# 05_eMMC.net
KiCad netlist of a schematic drawn in Altium Designer
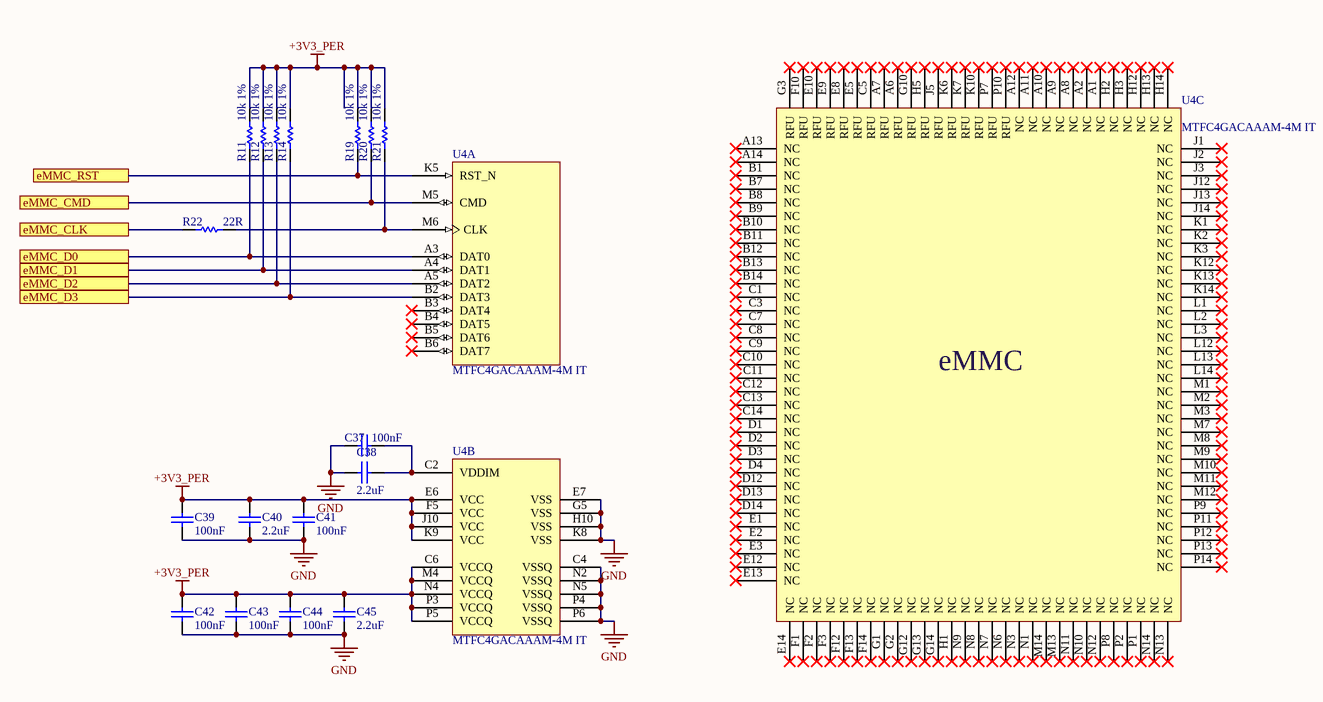
[diagram p0: 05. eMMC.SchDoc]

(export (version "E")
  (design (tool "Eeschema 10.0.6"))
  (components
    (comp (ref "C37")
      (value "100nF")
      (footprint "CAPC1005X60X30LL05T10")
      (description "Chip Capacitor, 0.1 uF, +/- 10%, 16 V, -55 to 125 degC, 0402 (1005 Metric), RoHS, Tape and Reel")
      (fields (field (name "VOLTAGE") "16V") (field (name "TOLERANCE") "10%"))
      (libsource (lib "AM3358_DEV_BOARD") (part "CAP-NP-2"))
    )
    (comp (ref "C38")
      (value "2.2uF")
      (footprint "CAPC1608X90X35ML10T15")
      (description "CAP 2.2uF 10V ±10% 0603 (1608 Metric) Thickness 0.6mm SMD")
      (fields (field (name "MANUFACTURER") "Murata") (field (name "PART NUMBER") "GRM188R71A225KE15D"))
      (libsource (lib "Altium Content Vault") (part "CAP"))
    )
    (comp (ref "C39")
      (value "100nF")
      (footprint "CAPC1005X60X30LL05T10")
      (description "Chip Capacitor, 0.1 uF, +/- 10%, 16 V, -55 to 125 degC, 0402 (1005 Metric), RoHS, Tape and Reel")
      (fields (field (name "VOLTAGE") "16V") (field (name "TOLERANCE") "10%"))
      (libsource (lib "AM3358_DEV_BOARD") (part "CAP-NP-2"))
    )
    (comp (ref "C40")
      (value "2.2uF")
      (footprint "CAPC1005X60X30LL05T10")
      (description "CAP 2.2uF 10V ±10% 0603 (1608 Metric) Thickness 0.6mm SMD")
      (fields (field (name "MANUFACTURER") "Murata") (field (name "PART NUMBER") "GRM188R71A225KE15D"))
      (libsource (lib "AM3358_DEV_BOARD") (part "CAP"))
    )
    (comp (ref "C41")
      (value "100nF")
      (footprint "CAPC1005X60X30LL05T10")
      (description "Chip Capacitor, 0.1 uF, +/- 10%, 16 V, -55 to 125 degC, 0402 (1005 Metric), RoHS, Tape and Reel")
      (fields (field (name "VOLTAGE") "16V") (field (name "TOLERANCE") "10%"))
      (libsource (lib "AM3358_DEV_BOARD") (part "CAP-NP-2"))
    )
    (comp (ref "C42")
      (value "100nF")
      (footprint "CAPC1005X60X30LL05T10")
      (description "Chip Capacitor, 0.1 uF, +/- 10%, 16 V, -55 to 125 degC, 0402 (1005 Metric), RoHS, Tape and Reel")
      (fields (field (name "VOLTAGE") "16V") (field (name "TOLERANCE") "10%"))
      (libsource (lib "AM3358_DEV_BOARD") (part "CAP-NP-2"))
    )
    (comp (ref "C43")
      (value "100nF")
      (footprint "CAPC1005X60X30LL05T10")
      (description "Chip Capacitor, 0.1 uF, +/- 10%, 16 V, -55 to 125 degC, 0402 (1005 Metric), RoHS, Tape and Reel")
      (fields (field (name "VOLTAGE") "16V") (field (name "TOLERANCE") "10%"))
      (libsource (lib "AM3358_DEV_BOARD") (part "CAP-NP-2"))
    )
    (comp (ref "C44")
      (value "100nF")
      (footprint "CAPC1005X60X30LL05T10")
      (description "Chip Capacitor, 0.1 uF, +/- 10%, 16 V, -55 to 125 degC, 0402 (1005 Metric), RoHS, Tape and Reel")
      (fields (field (name "VOLTAGE") "16V") (field (name "TOLERANCE") "10%"))
      (libsource (lib "AM3358_DEV_BOARD") (part "CAP-NP-2"))
    )
    (comp (ref "C45")
      (value "2.2uF")
      (footprint "CAPC1608X90X35ML10T15")
      (description "CAP 2.2uF 10V ±10% 0603 (1608 Metric) Thickness 0.6mm SMD")
      (fields (field (name "MANUFACTURER") "Murata") (field (name "PART NUMBER") "GRM188R71A225KE15D"))
      (libsource (lib "Altium Content Vault") (part "CAP"))
    )
    (comp (ref "R11")
      (value "10k 1%")
      (footprint "RESC1005X40X25LL05T05")
      (description "10k 0.063W 1% 0402 (1005 Metric)  SMD")
      (fields (field (name "MANUFACTURER") "Vishay Dale") (field (name "PART NUMBER") "CRCW040210K0FKED"))
      (libsource (lib "AM3358_DEV_BOARD") (part "RES"))
    )
    (comp (ref "R12")
      (value "10k 1%")
      (footprint "RESC1005X40X25LL05T05")
      (description "10k 0.063W 1% 0402 (1005 Metric)  SMD")
      (fields (field (name "MANUFACTURER") "Vishay Dale") (field (name "PART NUMBER") "CRCW040210K0FKED"))
      (libsource (lib "AM3358_DEV_BOARD") (part "RES"))
    )
    (comp (ref "R13")
      (value "10k 1%")
      (footprint "RESC1005X40X25LL05T05")
      (description "10k 0.063W 1% 0402 (1005 Metric)  SMD")
      (fields (field (name "MANUFACTURER") "Vishay Dale") (field (name "PART NUMBER") "CRCW040210K0FKED"))
      (libsource (lib "AM3358_DEV_BOARD") (part "RES"))
    )
    (comp (ref "R14")
      (value "10k 1%")
      (footprint "RESC1005X40X25LL05T05")
      (description "10k 0.063W 1% 0402 (1005 Metric)  SMD")
      (fields (field (name "MANUFACTURER") "Vishay Dale") (field (name "PART NUMBER") "CRCW040210K0FKED"))
      (libsource (lib "AM3358_DEV_BOARD") (part "RES"))
    )
    (comp (ref "R19")
      (value "10k 1%")
      (footprint "RESC1005X40X25LL05T05")
      (description "10k 0.063W 1% 0402 (1005 Metric)  SMD")
      (fields (field (name "MANUFACTURER") "Vishay Dale") (field (name "PART NUMBER") "CRCW040210K0FKED"))
      (libsource (lib "AM3358_DEV_BOARD") (part "RES"))
    )
    (comp (ref "R20")
      (value "10k 1%")
      (footprint "RESC1005X40X25LL05T05")
      (description "10k 0.063W 1% 0402 (1005 Metric)  SMD")
      (fields (field (name "MANUFACTURER") "Vishay Dale") (field (name "PART NUMBER") "CRCW040210K0FKED"))
      (libsource (lib "AM3358_DEV_BOARD") (part "RES"))
    )
    (comp (ref "R21")
      (value "10k 1%")
      (footprint "RESC1005X40X25LL05T05")
      (description "10k 0.063W 1% 0402 (1005 Metric)  SMD")
      (fields (field (name "MANUFACTURER") "Vishay Dale") (field (name "PART NUMBER") "CRCW040210K0FKED"))
      (libsource (lib "AM3358_DEV_BOARD") (part "RES"))
    )
    (comp (ref "R22")
      (value "22R")
      (footprint "RESC1005X40X25LL05T05")
      (description "Chip Resistor, 22 Ohm, +/- 1%, 0.1 W, -55 to 155 degC, 0402 (1005 Metric), RoHS, Tape and Reel")
      (fields (field (name "PARTNUMBER") "ERJ-2RKF22R0X") (field (name "TOLERANCE") "1%"))
      (libsource (lib "AM3358_DEV_BOARD") (part "RES-2"))
    )
    (comp (ref "U4")
      (value "MTFC4GACAAAM-4M IT")
      (footprint "VFBGA-153")
      (description "e·MMC Memory, 4 Gb, 2.7 to 3.6 V, -40 to 85 degC, 153-Ball VFBGA, RoHS")
      (fields (field (name "MANUFACTURER") "Micron"))
      (libsource (lib "AM3358_DEV_BOARD") (part "CMP-2000-05234-1"))
    )
  )
  (nets
    (net (code "1") (name "+3V3_PER") (class "Default")
      (node (ref "C39") (pin "2") (pinfunction "2_2") (pintype "passive"))
      (node (ref "C40") (pin "2") (pinfunction "2_2") (pintype "passive"))
      (node (ref "C41") (pin "2") (pinfunction "2_2") (pintype "passive"))
      (node (ref "C42") (pin "2") (pinfunction "2_2") (pintype "passive"))
      (node (ref "C43") (pin "2") (pinfunction "2_2") (pintype "passive"))
      (node (ref "C44") (pin "2") (pinfunction "2_2") (pintype "passive"))
      (node (ref "C45") (pin "2") (pinfunction "2_2") (pintype "passive"))
      (node (ref "R11") (pin "2") (pinfunction "2_2") (pintype "passive"))
      (node (ref "R12") (pin "2") (pinfunction "2_2") (pintype "passive"))
      (node (ref "R13") (pin "2") (pinfunction "2_2") (pintype "passive"))
      (node (ref "R14") (pin "2") (pinfunction "2_2") (pintype "passive"))
      (node (ref "R19") (pin "2") (pinfunction "2_2") (pintype "passive"))
      (node (ref "R20") (pin "2") (pinfunction "2_2") (pintype "passive"))
      (node (ref "R21") (pin "2") (pinfunction "2_2") (pintype "passive"))
      (node (ref "U4") (pin "C6") (pinfunction "VCCQ_C6") (pintype "power_in"))
      (node (ref "U4") (pin "E6") (pinfunction "VCC_E6") (pintype "power_in"))
      (node (ref "U4") (pin "F5") (pinfunction "VCC_F5") (pintype "power_in"))
      (node (ref "U4") (pin "J10") (pinfunction "VCC_J10") (pintype "power_in"))
      (node (ref "U4") (pin "K9") (pinfunction "VCC_K9") (pintype "power_in"))
      (node (ref "U4") (pin "M4") (pinfunction "VCCQ_M4") (pintype "power_in"))
      (node (ref "U4") (pin "N4") (pinfunction "VCCQ_N4") (pintype "power_in"))
      (node (ref "U4") (pin "P3") (pinfunction "VCCQ_P3") (pintype "power_in"))
      (node (ref "U4") (pin "P5") (pinfunction "VCCQ_P5") (pintype "power_in"))
    )
    (net (code "2") (name "/eMMC_CLK") (class "Default")
      (node (ref "R22") (pin "1") (pinfunction "1_1") (pintype "passive"))
    )
    (net (code "3") (name "/eMMC_CMD") (class "Default")
      (node (ref "R20") (pin "1") (pinfunction "1_1") (pintype "passive"))
      (node (ref "U4") (pin "M5") (pinfunction "CMD_M5") (pintype "bidirectional"))
    )
    (net (code "4") (name "/eMMC_D0") (class "Default")
      (node (ref "R11") (pin "1") (pinfunction "1_1") (pintype "passive"))
      (node (ref "U4") (pin "A3") (pinfunction "DAT0_A3") (pintype "bidirectional"))
    )
    (net (code "5") (name "/eMMC_D1") (class "Default")
      (node (ref "R12") (pin "1") (pinfunction "1_1") (pintype "passive"))
      (node (ref "U4") (pin "A4") (pinfunction "DAT1_A4") (pintype "bidirectional"))
    )
    (net (code "6") (name "/eMMC_D2") (class "Default")
      (node (ref "R13") (pin "1") (pinfunction "1_1") (pintype "passive"))
      (node (ref "U4") (pin "A5") (pinfunction "DAT2_A5") (pintype "bidirectional"))
    )
    (net (code "7") (name "/eMMC_D3") (class "Default")
      (node (ref "R14") (pin "1") (pinfunction "1_1") (pintype "passive"))
      (node (ref "U4") (pin "B2") (pinfunction "DAT3_B2") (pintype "bidirectional"))
    )
    (net (code "8") (name "/eMMC_RST") (class "Default")
      (node (ref "R19") (pin "1") (pinfunction "1_1") (pintype "passive"))
      (node (ref "U4") (pin "K5") (pinfunction "RST_N_K5") (pintype "input"))
    )
    (net (code "9") (name "GND") (class "Default")
      (node (ref "C37") (pin "2") (pinfunction "2_2") (pintype "passive"))
      (node (ref "C38") (pin "2") (pinfunction "2_2") (pintype "passive"))
      (node (ref "C39") (pin "1") (pinfunction "1_1") (pintype "passive"))
      (node (ref "C40") (pin "1") (pinfunction "1_1") (pintype "passive"))
      (node (ref "C41") (pin "1") (pinfunction "1_1") (pintype "passive"))
      (node (ref "C42") (pin "1") (pinfunction "1_1") (pintype "passive"))
      (node (ref "C43") (pin "1") (pinfunction "1_1") (pintype "passive"))
      (node (ref "C44") (pin "1") (pinfunction "1_1") (pintype "passive"))
      (node (ref "C45") (pin "1") (pinfunction "1_1") (pintype "passive"))
      (node (ref "U4") (pin "C4") (pinfunction "VSSQ_C4") (pintype "power_in"))
      (node (ref "U4") (pin "E7") (pinfunction "VSS_E7") (pintype "power_in"))
      (node (ref "U4") (pin "G5") (pinfunction "VSS_G5") (pintype "power_in"))
      (node (ref "U4") (pin "H10") (pinfunction "VSS_H10") (pintype "power_in"))
      (node (ref "U4") (pin "K8") (pinfunction "VSS_K8") (pintype "power_in"))
      (node (ref "U4") (pin "N2") (pinfunction "VSSQ_N2") (pintype "power_in"))
      (node (ref "U4") (pin "N5") (pinfunction "VSSQ_N5") (pintype "power_in"))
      (node (ref "U4") (pin "P4") (pinfunction "VSSQ_P4") (pintype "power_in"))
      (node (ref "U4") (pin "P6") (pinfunction "VSSQ_P6") (pintype "power_in"))
    )
    (net (code "10") (name "Net-(U4A-CLK)") (class "Default")
      (node (ref "R21") (pin "1") (pinfunction "1_1") (pintype "passive"))
      (node (ref "R22") (pin "2") (pinfunction "2_2") (pintype "passive"))
      (node (ref "U4") (pin "M6") (pinfunction "CLK_M6") (pintype "input"))
    )
    (net (code "11") (name "Net-(U4B-VDDIM)") (class "Default")
      (node (ref "C37") (pin "1") (pinfunction "1_1") (pintype "passive"))
      (node (ref "C38") (pin "1") (pinfunction "1_1") (pintype "passive"))
      (node (ref "U4") (pin "C2") (pinfunction "VDDIM_C2") (pintype "power_in"))
    )
    (net (code "12") (name "unconnected-(U4A-DAT4-PadB3)") (class "Default")
      (node (ref "U4") (pin "B3") (pinfunction "DAT4_B3") (pintype "bidirectional+no_connect"))
    )
    (net (code "13") (name "unconnected-(U4A-DAT5-PadB4)") (class "Default")
      (node (ref "U4") (pin "B4") (pinfunction "DAT5_B4") (pintype "bidirectional+no_connect"))
    )
    (net (code "14") (name "unconnected-(U4A-DAT6-PadB5)") (class "Default")
      (node (ref "U4") (pin "B5") (pinfunction "DAT6_B5") (pintype "bidirectional+no_connect"))
    )
    (net (code "15") (name "unconnected-(U4A-DAT7-PadB6)") (class "Default")
      (node (ref "U4") (pin "B6") (pinfunction "DAT7_B6") (pintype "bidirectional+no_connect"))
    )
    (net (code "16") (name "unconnected-(U4C-NC-PadA1)") (class "Default")
      (node (ref "U4") (pin "A1") (pinfunction "NC_A1") (pintype "passive+no_connect"))
    )
    (net (code "17") (name "unconnected-(U4C-NC-PadA2)") (class "Default")
      (node (ref "U4") (pin "A2") (pinfunction "NC_A2") (pintype "passive+no_connect"))
    )
    (net (code "18") (name "unconnected-(U4C-NC-PadA8)") (class "Default")
      (node (ref "U4") (pin "A8") (pinfunction "NC_A8") (pintype "passive+no_connect"))
    )
    (net (code "19") (name "unconnected-(U4C-NC-PadA9)") (class "Default")
      (node (ref "U4") (pin "A9") (pinfunction "NC_A9") (pintype "passive+no_connect"))
    )
    (net (code "20") (name "unconnected-(U4C-NC-PadA10)") (class "Default")
      (node (ref "U4") (pin "A10") (pinfunction "NC_A10") (pintype "passive+no_connect"))
    )
    (net (code "21") (name "unconnected-(U4C-NC-PadA11)") (class "Default")
      (node (ref "U4") (pin "A11") (pinfunction "NC_A11") (pintype "passive+no_connect"))
    )
    (net (code "22") (name "unconnected-(U4C-NC-PadA12)") (class "Default")
      (node (ref "U4") (pin "A12") (pinfunction "NC_A12") (pintype "passive+no_connect"))
    )
    (net (code "23") (name "unconnected-(U4C-NC-PadA13)") (class "Default")
      (node (ref "U4") (pin "A13") (pinfunction "NC_A13") (pintype "passive+no_connect"))
    )
    (net (code "24") (name "unconnected-(U4C-NC-PadA14)") (class "Default")
      (node (ref "U4") (pin "A14") (pinfunction "NC_A14") (pintype "passive+no_connect"))
    )
    (net (code "25") (name "unconnected-(U4C-NC-PadB1)") (class "Default")
      (node (ref "U4") (pin "B1") (pinfunction "NC_B1") (pintype "passive+no_connect"))
    )
    (net (code "26") (name "unconnected-(U4C-NC-PadB7)") (class "Default")
      (node (ref "U4") (pin "B7") (pinfunction "NC_B7") (pintype "passive+no_connect"))
    )
    (net (code "27") (name "unconnected-(U4C-NC-PadB8)") (class "Default")
      (node (ref "U4") (pin "B8") (pinfunction "NC_B8") (pintype "passive+no_connect"))
    )
    (net (code "28") (name "unconnected-(U4C-NC-PadB9)") (class "Default")
      (node (ref "U4") (pin "B9") (pinfunction "NC_B9") (pintype "passive+no_connect"))
    )
    (net (code "29") (name "unconnected-(U4C-NC-PadB10)") (class "Default")
      (node (ref "U4") (pin "B10") (pinfunction "NC_B10") (pintype "passive+no_connect"))
    )
    (net (code "30") (name "unconnected-(U4C-NC-PadB11)") (class "Default")
      (node (ref "U4") (pin "B11") (pinfunction "NC_B11") (pintype "passive+no_connect"))
    )
    (net (code "31") (name "unconnected-(U4C-NC-PadB12)") (class "Default")
      (node (ref "U4") (pin "B12") (pinfunction "NC_B12") (pintype "passive+no_connect"))
    )
    (net (code "32") (name "unconnected-(U4C-NC-PadB13)") (class "Default")
      (node (ref "U4") (pin "B13") (pinfunction "NC_B13") (pintype "passive+no_connect"))
    )
    (net (code "33") (name "unconnected-(U4C-NC-PadB14)") (class "Default")
      (node (ref "U4") (pin "B14") (pinfunction "NC_B14") (pintype "passive+no_connect"))
    )
    (net (code "34") (name "unconnected-(U4C-NC-PadC1)") (class "Default")
      (node (ref "U4") (pin "C1") (pinfunction "NC_C1") (pintype "passive+no_connect"))
    )
    (net (code "35") (name "unconnected-(U4C-NC-PadC3)") (class "Default")
      (node (ref "U4") (pin "C3") (pinfunction "NC_C3") (pintype "passive+no_connect"))
    )
    (net (code "36") (name "unconnected-(U4C-NC-PadC7)") (class "Default")
      (node (ref "U4") (pin "C7") (pinfunction "NC_C7") (pintype "passive+no_connect"))
    )
    (net (code "37") (name "unconnected-(U4C-NC-PadC8)") (class "Default")
      (node (ref "U4") (pin "C8") (pinfunction "NC_C8") (pintype "passive+no_connect"))
    )
    (net (code "38") (name "unconnected-(U4C-NC-PadC9)") (class "Default")
      (node (ref "U4") (pin "C9") (pinfunction "NC_C9") (pintype "passive+no_connect"))
    )
    (net (code "39") (name "unconnected-(U4C-NC-PadC10)") (class "Default")
      (node (ref "U4") (pin "C10") (pinfunction "NC_C10") (pintype "passive+no_connect"))
    )
    (net (code "40") (name "unconnected-(U4C-NC-PadC11)") (class "Default")
      (node (ref "U4") (pin "C11") (pinfunction "NC_C11") (pintype "passive+no_connect"))
    )
    (net (code "41") (name "unconnected-(U4C-NC-PadC12)") (class "Default")
      (node (ref "U4") (pin "C12") (pinfunction "NC_C12") (pintype "passive+no_connect"))
    )
    (net (code "42") (name "unconnected-(U4C-NC-PadC13)") (class "Default")
      (node (ref "U4") (pin "C13") (pinfunction "NC_C13") (pintype "passive+no_connect"))
    )
    (net (code "43") (name "unconnected-(U4C-NC-PadC14)") (class "Default")
      (node (ref "U4") (pin "C14") (pinfunction "NC_C14") (pintype "passive+no_connect"))
    )
    (net (code "44") (name "unconnected-(U4C-NC-PadD1)") (class "Default")
      (node (ref "U4") (pin "D1") (pinfunction "NC_D1") (pintype "passive+no_connect"))
    )
    (net (code "45") (name "unconnected-(U4C-NC-PadD2)") (class "Default")
      (node (ref "U4") (pin "D2") (pinfunction "NC_D2") (pintype "passive+no_connect"))
    )
    (net (code "46") (name "unconnected-(U4C-NC-PadD3)") (class "Default")
      (node (ref "U4") (pin "D3") (pinfunction "NC_D3") (pintype "passive+no_connect"))
    )
    (net (code "47") (name "unconnected-(U4C-NC-PadD4)") (class "Default")
      (node (ref "U4") (pin "D4") (pinfunction "NC_D4") (pintype "passive+no_connect"))
    )
    (net (code "48") (name "unconnected-(U4C-NC-PadD12)") (class "Default")
      (node (ref "U4") (pin "D12") (pinfunction "NC_D12") (pintype "passive+no_connect"))
    )
    (net (code "49") (name "unconnected-(U4C-NC-PadD13)") (class "Default")
      (node (ref "U4") (pin "D13") (pinfunction "NC_D13") (pintype "passive+no_connect"))
    )
    (net (code "50") (name "unconnected-(U4C-NC-PadD14)") (class "Default")
      (node (ref "U4") (pin "D14") (pinfunction "NC_D14") (pintype "passive+no_connect"))
    )
    (net (code "51") (name "unconnected-(U4C-NC-PadE1)") (class "Default")
      (node (ref "U4") (pin "E1") (pinfunction "NC_E1") (pintype "passive+no_connect"))
    )
    (net (code "52") (name "unconnected-(U4C-NC-PadE2)") (class "Default")
      (node (ref "U4") (pin "E2") (pinfunction "NC_E2") (pintype "passive+no_connect"))
    )
    (net (code "53") (name "unconnected-(U4C-NC-PadE3)") (class "Default")
      (node (ref "U4") (pin "E3") (pinfunction "NC_E3") (pintype "passive+no_connect"))
    )
    (net (code "54") (name "unconnected-(U4C-NC-PadE12)") (class "Default")
      (node (ref "U4") (pin "E12") (pinfunction "NC_E12") (pintype "passive+no_connect"))
    )
    (net (code "55") (name "unconnected-(U4C-NC-PadE13)") (class "Default")
      (node (ref "U4") (pin "E13") (pinfunction "NC_E13") (pintype "passive+no_connect"))
    )
    (net (code "56") (name "unconnected-(U4C-NC-PadE14)") (class "Default")
      (node (ref "U4") (pin "E14") (pinfunction "NC_E14") (pintype "passive+no_connect"))
    )
    (net (code "57") (name "unconnected-(U4C-NC-PadF1)") (class "Default")
      (node (ref "U4") (pin "F1") (pinfunction "NC_F1") (pintype "passive+no_connect"))
    )
    (net (code "58") (name "unconnected-(U4C-NC-PadF2)") (class "Default")
      (node (ref "U4") (pin "F2") (pinfunction "NC_F2") (pintype "passive+no_connect"))
    )
    (net (code "59") (name "unconnected-(U4C-NC-PadF3)") (class "Default")
      (node (ref "U4") (pin "F3") (pinfunction "NC_F3") (pintype "passive+no_connect"))
    )
    (net (code "60") (name "unconnected-(U4C-NC-PadF12)") (class "Default")
      (node (ref "U4") (pin "F12") (pinfunction "NC_F12") (pintype "passive+no_connect"))
    )
    (net (code "61") (name "unconnected-(U4C-NC-PadF13)") (class "Default")
      (node (ref "U4") (pin "F13") (pinfunction "NC_F13") (pintype "passive+no_connect"))
    )
    (net (code "62") (name "unconnected-(U4C-NC-PadF14)") (class "Default")
      (node (ref "U4") (pin "F14") (pinfunction "NC_F14") (pintype "passive+no_connect"))
    )
    (net (code "63") (name "unconnected-(U4C-NC-PadG1)") (class "Default")
      (node (ref "U4") (pin "G1") (pinfunction "NC_G1") (pintype "passive+no_connect"))
    )
    (net (code "64") (name "unconnected-(U4C-NC-PadG2)") (class "Default")
      (node (ref "U4") (pin "G2") (pinfunction "NC_G2") (pintype "passive+no_connect"))
    )
    (net (code "65") (name "unconnected-(U4C-NC-PadG12)") (class "Default")
      (node (ref "U4") (pin "G12") (pinfunction "NC_G12") (pintype "passive+no_connect"))
    )
    (net (code "66") (name "unconnected-(U4C-NC-PadG13)") (class "Default")
      (node (ref "U4") (pin "G13") (pinfunction "NC_G13") (pintype "passive+no_connect"))
    )
    (net (code "67") (name "unconnected-(U4C-NC-PadG14)") (class "Default")
      (node (ref "U4") (pin "G14") (pinfunction "NC_G14") (pintype "passive+no_connect"))
    )
    (net (code "68") (name "unconnected-(U4C-NC-PadH1)") (class "Default")
      (node (ref "U4") (pin "H1") (pinfunction "NC_H1") (pintype "passive+no_connect"))
    )
    (net (code "69") (name "unconnected-(U4C-NC-PadH2)") (class "Default")
      (node (ref "U4") (pin "H2") (pinfunction "NC_H2") (pintype "passive+no_connect"))
    )
    (net (code "70") (name "unconnected-(U4C-NC-PadH3)") (class "Default")
      (node (ref "U4") (pin "H3") (pinfunction "NC_H3") (pintype "passive+no_connect"))
    )
    (net (code "71") (name "unconnected-(U4C-NC-PadH12)") (class "Default")
      (node (ref "U4") (pin "H12") (pinfunction "NC_H12") (pintype "passive+no_connect"))
    )
    (net (code "72") (name "unconnected-(U4C-NC-PadH13)") (class "Default")
      (node (ref "U4") (pin "H13") (pinfunction "NC_H13") (pintype "passive+no_connect"))
    )
    (net (code "73") (name "unconnected-(U4C-NC-PadH14)") (class "Default")
      (node (ref "U4") (pin "H14") (pinfunction "NC_H14") (pintype "passive+no_connect"))
    )
    (net (code "74") (name "unconnected-(U4C-NC-PadJ1)") (class "Default")
      (node (ref "U4") (pin "J1") (pinfunction "NC_J1") (pintype "passive+no_connect"))
    )
    (net (code "75") (name "unconnected-(U4C-NC-PadJ2)") (class "Default")
      (node (ref "U4") (pin "J2") (pinfunction "NC_J2") (pintype "passive+no_connect"))
    )
    (net (code "76") (name "unconnected-(U4C-NC-PadJ3)") (class "Default")
      (node (ref "U4") (pin "J3") (pinfunction "NC_J3") (pintype "passive+no_connect"))
    )
    (net (code "77") (name "unconnected-(U4C-NC-PadJ12)") (class "Default")
      (node (ref "U4") (pin "J12") (pinfunction "NC_J12") (pintype "passive+no_connect"))
    )
    (net (code "78") (name "unconnected-(U4C-NC-PadJ13)") (class "Default")
      (node (ref "U4") (pin "J13") (pinfunction "NC_J13") (pintype "passive+no_connect"))
    )
    (net (code "79") (name "unconnected-(U4C-NC-PadJ14)") (class "Default")
      (node (ref "U4") (pin "J14") (pinfunction "NC_J14") (pintype "passive+no_connect"))
    )
    (net (code "80") (name "unconnected-(U4C-NC-PadK1)") (class "Default")
      (node (ref "U4") (pin "K1") (pinfunction "NC_K1") (pintype "passive+no_connect"))
    )
    (net (code "81") (name "unconnected-(U4C-NC-PadK2)") (class "Default")
      (node (ref "U4") (pin "K2") (pinfunction "NC_K2") (pintype "passive+no_connect"))
    )
    (net (code "82") (name "unconnected-(U4C-NC-PadK3)") (class "Default")
      (node (ref "U4") (pin "K3") (pinfunction "NC_K3") (pintype "passive+no_connect"))
    )
    (net (code "83") (name "unconnected-(U4C-NC-PadK12)") (class "Default")
      (node (ref "U4") (pin "K12") (pinfunction "NC_K12") (pintype "passive+no_connect"))
    )
    (net (code "84") (name "unconnected-(U4C-NC-PadK13)") (class "Default")
      (node (ref "U4") (pin "K13") (pinfunction "NC_K13") (pintype "passive+no_connect"))
    )
    (net (code "85") (name "unconnected-(U4C-NC-PadK14)") (class "Default")
      (node (ref "U4") (pin "K14") (pinfunction "NC_K14") (pintype "passive+no_connect"))
    )
    (net (code "86") (name "unconnected-(U4C-NC-PadL1)") (class "Default")
      (node (ref "U4") (pin "L1") (pinfunction "NC_L1") (pintype "passive+no_connect"))
    )
    (net (code "87") (name "unconnected-(U4C-NC-PadL2)") (class "Default")
      (node (ref "U4") (pin "L2") (pinfunction "NC_L2") (pintype "passive+no_connect"))
    )
    (net (code "88") (name "unconnected-(U4C-NC-PadL3)") (class "Default")
      (node (ref "U4") (pin "L3") (pinfunction "NC_L3") (pintype "passive+no_connect"))
    )
    (net (code "89") (name "unconnected-(U4C-NC-PadL12)") (class "Default")
      (node (ref "U4") (pin "L12") (pinfunction "NC_L12") (pintype "passive+no_connect"))
    )
    (net (code "90") (name "unconnected-(U4C-NC-PadL13)") (class "Default")
      (node (ref "U4") (pin "L13") (pinfunction "NC_L13") (pintype "passive+no_connect"))
    )
    (net (code "91") (name "unconnected-(U4C-NC-PadL14)") (class "Default")
      (node (ref "U4") (pin "L14") (pinfunction "NC_L14") (pintype "passive+no_connect"))
    )
    (net (code "92") (name "unconnected-(U4C-NC-PadM1)") (class "Default")
      (node (ref "U4") (pin "M1") (pinfunction "NC_M1") (pintype "passive+no_connect"))
    )
    (net (code "93") (name "unconnected-(U4C-NC-PadM2)") (class "Default")
      (node (ref "U4") (pin "M2") (pinfunction "NC_M2") (pintype "passive+no_connect"))
    )
    (net (code "94") (name "unconnected-(U4C-NC-PadM3)") (class "Default")
      (node (ref "U4") (pin "M3") (pinfunction "NC_M3") (pintype "passive+no_connect"))
    )
    (net (code "95") (name "unconnected-(U4C-NC-PadM7)") (class "Default")
      (node (ref "U4") (pin "M7") (pinfunction "NC_M7") (pintype "passive+no_connect"))
    )
    (net (code "96") (name "unconnected-(U4C-NC-PadM8)") (class "Default")
      (node (ref "U4") (pin "M8") (pinfunction "NC_M8") (pintype "passive+no_connect"))
    )
    (net (code "97") (name "unconnected-(U4C-NC-PadM9)") (class "Default")
      (node (ref "U4") (pin "M9") (pinfunction "NC_M9") (pintype "passive+no_connect"))
    )
    (net (code "98") (name "unconnected-(U4C-NC-PadM10)") (class "Default")
      (node (ref "U4") (pin "M10") (pinfunction "NC_M10") (pintype "passive+no_connect"))
    )
    (net (code "99") (name "unconnected-(U4C-NC-PadM11)") (class "Default")
      (node (ref "U4") (pin "M11") (pinfunction "NC_M11") (pintype "passive+no_connect"))
    )
    (net (code "100") (name "unconnected-(U4C-NC-PadM12)") (class "Default")
      (node (ref "U4") (pin "M12") (pinfunction "NC_M12") (pintype "passive+no_connect"))
    )
    (net (code "101") (name "unconnected-(U4C-NC-PadM13)") (class "Default")
      (node (ref "U4") (pin "M13") (pinfunction "NC_M13") (pintype "passive+no_connect"))
    )
    (net (code "102") (name "unconnected-(U4C-NC-PadM14)") (class "Default")
      (node (ref "U4") (pin "M14") (pinfunction "NC_M14") (pintype "passive+no_connect"))
    )
    (net (code "103") (name "unconnected-(U4C-NC-PadN1)") (class "Default")
      (node (ref "U4") (pin "N1") (pinfunction "NC_N1") (pintype "passive+no_connect"))
    )
    (net (code "104") (name "unconnected-(U4C-NC-PadN3)") (class "Default")
      (node (ref "U4") (pin "N3") (pinfunction "NC_N3") (pintype "passive+no_connect"))
    )
    (net (code "105") (name "unconnected-(U4C-NC-PadN6)") (class "Default")
      (node (ref "U4") (pin "N6") (pinfunction "NC_N6") (pintype "passive+no_connect"))
    )
    (net (code "106") (name "unconnected-(U4C-NC-PadN7)") (class "Default")
      (node (ref "U4") (pin "N7") (pinfunction "NC_N7") (pintype "passive+no_connect"))
    )
    (net (code "107") (name "unconnected-(U4C-NC-PadN8)") (class "Default")
      (node (ref "U4") (pin "N8") (pinfunction "NC_N8") (pintype "passive+no_connect"))
    )
    (net (code "108") (name "unconnected-(U4C-NC-PadN9)") (class "Default")
      (node (ref "U4") (pin "N9") (pinfunction "NC_N9") (pintype "passive+no_connect"))
    )
    (net (code "109") (name "unconnected-(U4C-NC-PadN10)") (class "Default")
      (node (ref "U4") (pin "N10") (pinfunction "NC_N10") (pintype "passive+no_connect"))
    )
    (net (code "110") (name "unconnected-(U4C-NC-PadN11)") (class "Default")
      (node (ref "U4") (pin "N11") (pinfunction "NC_N11") (pintype "passive+no_connect"))
    )
    (net (code "111") (name "unconnected-(U4C-NC-PadN12)") (class "Default")
      (node (ref "U4") (pin "N12") (pinfunction "NC_N12") (pintype "passive+no_connect"))
    )
    (net (code "112") (name "unconnected-(U4C-NC-PadN13)") (class "Default")
      (node (ref "U4") (pin "N13") (pinfunction "NC_N13") (pintype "passive+no_connect"))
    )
    (net (code "113") (name "unconnected-(U4C-NC-PadN14)") (class "Default")
      (node (ref "U4") (pin "N14") (pinfunction "NC_N14") (pintype "passive+no_connect"))
    )
    (net (code "114") (name "unconnected-(U4C-NC-PadP1)") (class "Default")
      (node (ref "U4") (pin "P1") (pinfunction "NC_P1") (pintype "passive+no_connect"))
    )
    (net (code "115") (name "unconnected-(U4C-NC-PadP2)") (class "Default")
      (node (ref "U4") (pin "P2") (pinfunction "NC_P2") (pintype "passive+no_connect"))
    )
    (net (code "116") (name "unconnected-(U4C-NC-PadP8)") (class "Default")
      (node (ref "U4") (pin "P8") (pinfunction "NC_P8") (pintype "passive+no_connect"))
    )
    (net (code "117") (name "unconnected-(U4C-NC-PadP9)") (class "Default")
      (node (ref "U4") (pin "P9") (pinfunction "NC_P9") (pintype "passive+no_connect"))
    )
    (net (code "118") (name "unconnected-(U4C-NC-PadP11)") (class "Default")
      (node (ref "U4") (pin "P11") (pinfunction "NC_P11") (pintype "passive+no_connect"))
    )
    (net (code "119") (name "unconnected-(U4C-NC-PadP12)") (class "Default")
      (node (ref "U4") (pin "P12") (pinfunction "NC_P12") (pintype "passive+no_connect"))
    )
    (net (code "120") (name "unconnected-(U4C-NC-PadP13)") (class "Default")
      (node (ref "U4") (pin "P13") (pinfunction "NC_P13") (pintype "passive+no_connect"))
    )
    (net (code "121") (name "unconnected-(U4C-NC-PadP14)") (class "Default")
      (node (ref "U4") (pin "P14") (pinfunction "NC_P14") (pintype "passive+no_connect"))
    )
    (net (code "122") (name "unconnected-(U4C-RFU-PadA6)") (class "Default")
      (node (ref "U4") (pin "A6") (pinfunction "RFU_A6") (pintype "passive+no_connect"))
    )
    (net (code "123") (name "unconnected-(U4C-RFU-PadA7)") (class "Default")
      (node (ref "U4") (pin "A7") (pinfunction "RFU_A7") (pintype "passive+no_connect"))
    )
    (net (code "124") (name "unconnected-(U4C-RFU-PadC5)") (class "Default")
      (node (ref "U4") (pin "C5") (pinfunction "RFU_C5") (pintype "passive+no_connect"))
    )
    (net (code "125") (name "unconnected-(U4C-RFU-PadE5)") (class "Default")
      (node (ref "U4") (pin "E5") (pinfunction "RFU_E5") (pintype "passive+no_connect"))
    )
    (net (code "126") (name "unconnected-(U4C-RFU-PadE8)") (class "Default")
      (node (ref "U4") (pin "E8") (pinfunction "RFU_E8") (pintype "passive+no_connect"))
    )
    (net (code "127") (name "unconnected-(U4C-RFU-PadE9)") (class "Default")
      (node (ref "U4") (pin "E9") (pinfunction "RFU_E9") (pintype "passive+no_connect"))
    )
    (net (code "128") (name "unconnected-(U4C-RFU-PadE10)") (class "Default")
      (node (ref "U4") (pin "E10") (pinfunction "RFU_E10") (pintype "passive+no_connect"))
    )
    (net (code "129") (name "unconnected-(U4C-RFU-PadF10)") (class "Default")
      (node (ref "U4") (pin "F10") (pinfunction "RFU_F10") (pintype "passive+no_connect"))
    )
    (net (code "130") (name "unconnected-(U4C-RFU-PadG3)") (class "Default")
      (node (ref "U4") (pin "G3") (pinfunction "RFU_G3") (pintype "passive+no_connect"))
    )
    (net (code "131") (name "unconnected-(U4C-RFU-PadG10)") (class "Default")
      (node (ref "U4") (pin "G10") (pinfunction "RFU_G10") (pintype "passive+no_connect"))
    )
    (net (code "132") (name "unconnected-(U4C-RFU-PadH5)") (class "Default")
      (node (ref "U4") (pin "H5") (pinfunction "RFU_H5") (pintype "passive+no_connect"))
    )
    (net (code "133") (name "unconnected-(U4C-RFU-PadJ5)") (class "Default")
      (node (ref "U4") (pin "J5") (pinfunction "RFU_J5") (pintype "passive+no_connect"))
    )
    (net (code "134") (name "unconnected-(U4C-RFU-PadK6)") (class "Default")
      (node (ref "U4") (pin "K6") (pinfunction "RFU_K6") (pintype "passive+no_connect"))
    )
    (net (code "135") (name "unconnected-(U4C-RFU-PadK7)") (class "Default")
      (node (ref "U4") (pin "K7") (pinfunction "RFU_K7") (pintype "passive+no_connect"))
    )
    (net (code "136") (name "unconnected-(U4C-RFU-PadK10)") (class "Default")
      (node (ref "U4") (pin "K10") (pinfunction "RFU_K10") (pintype "passive+no_connect"))
    )
    (net (code "137") (name "unconnected-(U4C-RFU-PadP7)") (class "Default")
      (node (ref "U4") (pin "P7") (pinfunction "RFU_P7") (pintype "passive+no_connect"))
    )
    (net (code "138") (name "unconnected-(U4C-RFU-PadP10)") (class "Default")
      (node (ref "U4") (pin "P10") (pinfunction "RFU_P10") (pintype "passive+no_connect"))
    )
  )
)
